# FIPI_shematics.net
KiCad netlist of a schematic drawn in EAGLE
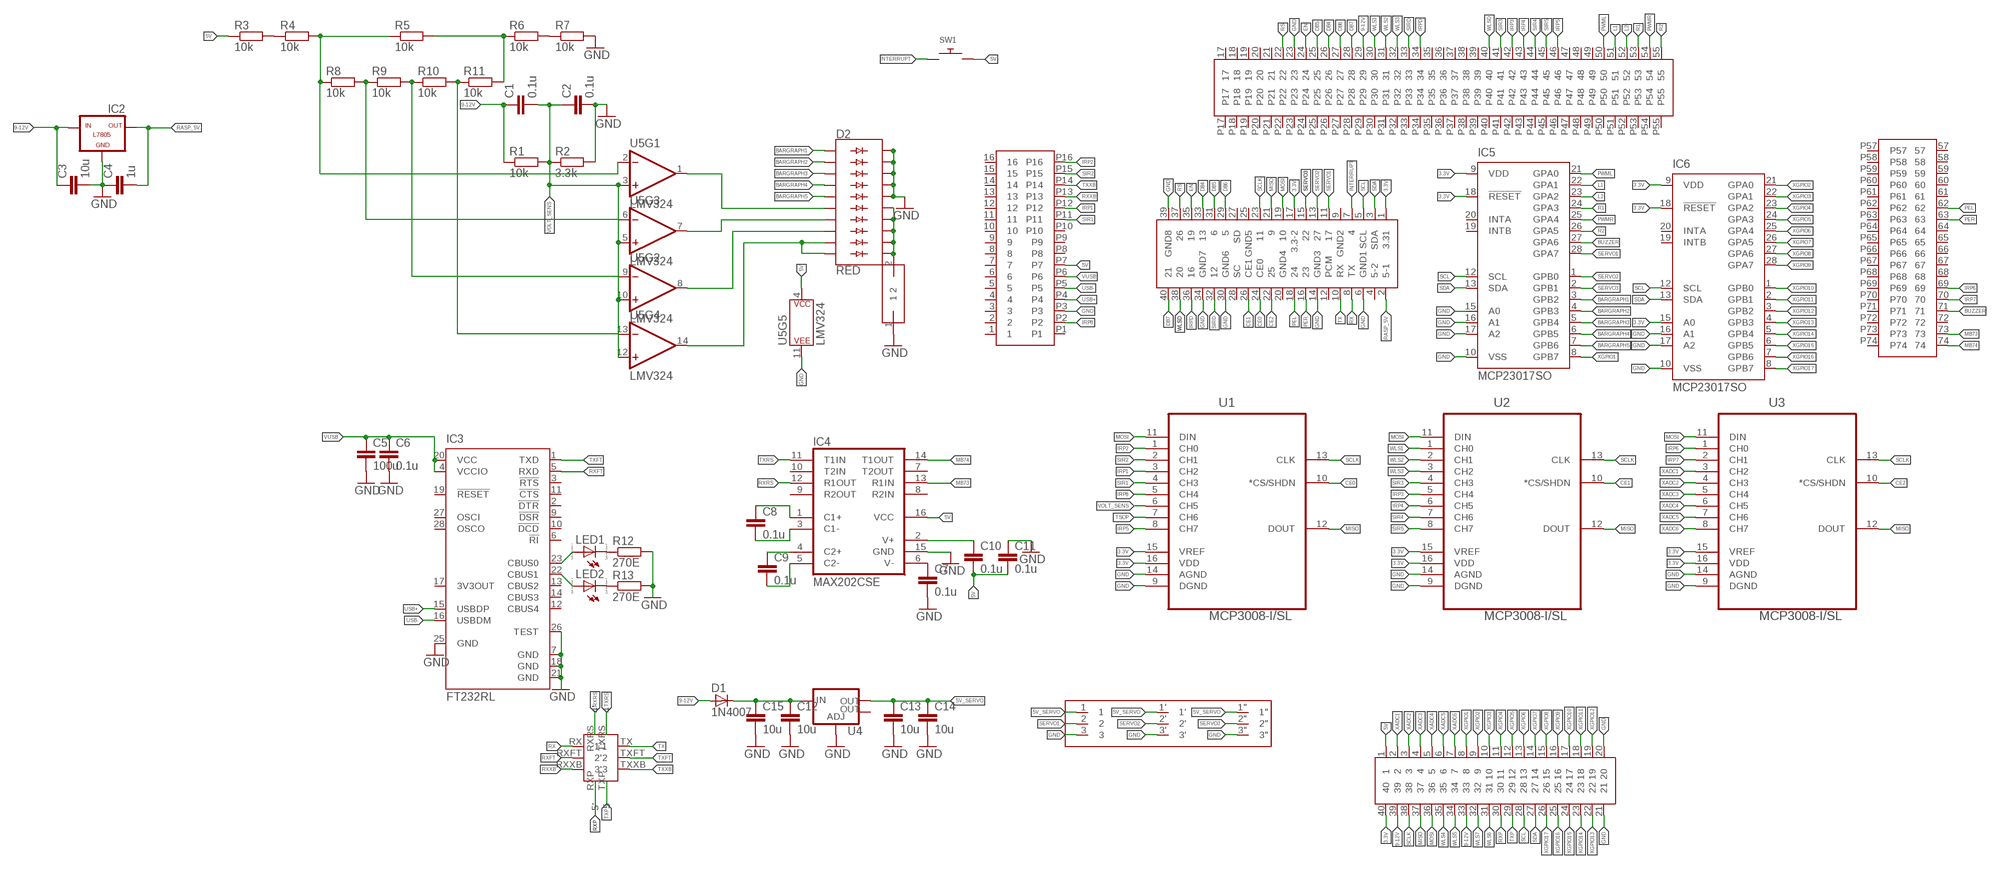
[diagram p0: schematic, sheet 1]

(export (version "E")
  (design (tool "Eeschema 10.0.6"))
  (components
    (comp (ref "C1")
      (value "0.1u")
      (footprint "eagle-import:C1206")
      (libsource (lib "eagle-import") (part "C-EUC1206"))
    )
    (comp (ref "C2")
      (value "0.1u")
      (footprint "eagle-import:C1206")
      (libsource (lib "eagle-import") (part "C-EUC1206"))
    )
    (comp (ref "C3")
      (value "10u")
      (footprint "eagle-import:C1206")
      (libsource (lib "eagle-import") (part "C-EUC1206"))
    )
    (comp (ref "C4")
      (value "1u")
      (footprint "eagle-import:C1206")
      (libsource (lib "eagle-import") (part "C-EUC1206"))
    )
    (comp (ref "C5")
      (value "100u")
      (footprint "eagle-import:C1206")
      (libsource (lib "eagle-import") (part "C-EUC1206"))
    )
    (comp (ref "C6")
      (value "0.1u")
      (footprint "eagle-import:C1206")
      (libsource (lib "eagle-import") (part "C-EUC1206"))
    )
    (comp (ref "C7")
      (value "0.1u")
      (footprint "eagle-import:C1206")
      (libsource (lib "eagle-import") (part "C-EUC1206"))
    )
    (comp (ref "C8")
      (value "0.1u")
      (footprint "eagle-import:C1206")
      (libsource (lib "eagle-import") (part "C-EUC1206"))
    )
    (comp (ref "C9")
      (value "0.1u")
      (footprint "eagle-import:C1206")
      (libsource (lib "eagle-import") (part "C-EUC1206"))
    )
    (comp (ref "C10")
      (value "0.1u")
      (footprint "eagle-import:C1206")
      (libsource (lib "eagle-import") (part "C-EUC1206"))
    )
    (comp (ref "C11")
      (value "0.1u")
      (footprint "eagle-import:C1206")
      (libsource (lib "eagle-import") (part "C-EUC1206"))
    )
    (comp (ref "C12")
      (value "10u")
      (footprint "eagle-import:C1206")
      (libsource (lib "eagle-import") (part "C-EUC1206"))
    )
    (comp (ref "C13")
      (value "10u")
      (footprint "eagle-import:C1206")
      (libsource (lib "eagle-import") (part "C-EUC1206"))
    )
    (comp (ref "C14")
      (value "10u")
      (footprint "eagle-import:C1206")
      (libsource (lib "eagle-import") (part "C-EUC1206"))
    )
    (comp (ref "C15")
      (value "10u")
      (footprint "eagle-import:C1206")
      (libsource (lib "eagle-import") (part "C-EUC1206"))
    )
    (comp (ref "D1")
      (value "1N4007")
      (footprint "eagle-import:SMA")
      (libsource (lib "eagle-import") (part "1N4007"))
    )
    (comp (ref "D2")
      (value "RED")
      (footprint "eagle-import:LED_BARGRAPH_10")
      (libsource (lib "eagle-import") (part "LED_BARGRAPH_10RED"))
    )
    (comp (ref "IC2")
      (value "L7805")
      (footprint "eagle-import:78XXL")
      (libsource (lib "eagle-import") (part "L7805"))
    )
    (comp (ref "IC3")
      (value "FT232RL")
      (footprint "eagle-import:SSOP28")
      (libsource (lib "eagle-import") (part "FT232RL"))
    )
    (comp (ref "IC4")
      (value "MAX202CSE")
      (footprint "eagle-import:SO16")
      (libsource (lib "eagle-import") (part "MAX202SEC"))
    )
    (comp (ref "IC5")
      (value "MCP23017SO")
      (footprint "eagle-import:SO28W")
      (libsource (lib "eagle-import") (part "MCP23017SO"))
    )
    (comp (ref "IC6")
      (value "MCP23017SO")
      (footprint "eagle-import:SO28W")
      (libsource (lib "eagle-import") (part "MCP23017SO"))
    )
    (comp (ref "LED1")
      (value "LED_E")
      (footprint "eagle-import:LED_1206")
      (libsource (lib "eagle-import") (part "LED_E"))
    )
    (comp (ref "LED2")
      (value "LED_E")
      (footprint "eagle-import:LED_1206")
      (libsource (lib "eagle-import") (part "LED_E"))
    )
    (comp (ref "R1")
      (value "10k")
      (footprint "eagle-import:M1206")
      (libsource (lib "eagle-import") (part "R-EU_M1206"))
    )
    (comp (ref "R2")
      (value "3.3k")
      (footprint "eagle-import:M1206")
      (libsource (lib "eagle-import") (part "R-EU_M1206"))
    )
    (comp (ref "R3")
      (value "10k")
      (footprint "eagle-import:M1206")
      (libsource (lib "eagle-import") (part "R-EU_M1206"))
    )
    (comp (ref "R4")
      (value "10k")
      (footprint "eagle-import:M1206")
      (libsource (lib "eagle-import") (part "R-EU_M1206"))
    )
    (comp (ref "R5")
      (value "10k")
      (footprint "eagle-import:M1206")
      (libsource (lib "eagle-import") (part "R-EU_M1206"))
    )
    (comp (ref "R6")
      (value "10k")
      (footprint "eagle-import:M1206")
      (libsource (lib "eagle-import") (part "R-EU_M1206"))
    )
    (comp (ref "R7")
      (value "10k")
      (footprint "eagle-import:M1206")
      (libsource (lib "eagle-import") (part "R-EU_M1206"))
    )
    (comp (ref "R8")
      (value "10k")
      (footprint "eagle-import:M1206")
      (libsource (lib "eagle-import") (part "R-EU_M1206"))
    )
    (comp (ref "R9")
      (value "10k")
      (footprint "eagle-import:M1206")
      (libsource (lib "eagle-import") (part "R-EU_M1206"))
    )
    (comp (ref "R10")
      (value "10k")
      (footprint "eagle-import:M1206")
      (libsource (lib "eagle-import") (part "R-EU_M1206"))
    )
    (comp (ref "R11")
      (value "10k")
      (footprint "eagle-import:M1206")
      (libsource (lib "eagle-import") (part "R-EU_M1206"))
    )
    (comp (ref "R12")
      (value "270E")
      (footprint "eagle-import:R1206")
      (libsource (lib "eagle-import") (part "R-EU_R1206"))
    )
    (comp (ref "R13")
      (value "270E")
      (footprint "eagle-import:R1206")
      (libsource (lib "eagle-import") (part "R-EU_R1206"))
    )
    (comp (ref "RASPPI")
      (value "MALE_HEADER")
      (footprint "eagle-import:MALE_HEADER_PACKAGE")
      (libsource (lib "eagle-import") (part "MALE_HEADER"))
    )
    (comp (ref "SW1")
      (value "SWITCH_PUSHBUTTONSOFTTOUCHSMD_SJ")
      (footprint "eagle-import:PUSHBUTTON_SMD_SJ")
      (libsource (lib "eagle-import") (part "SWITCH_PUSHBUTTONSOFTTOUCHSMD_SJ"))
    )
    (comp (ref "U$1")
      (value "BOARD")
      (footprint "eagle-import:FEMHEADER")
      (libsource (lib "eagle-import") (part "BOARD"))
    )
    (comp (ref "U$3")
      (value "SWITCH_RXTX")
      (footprint "eagle-import:SWITCH_RXTX")
      (libsource (lib "eagle-import") (part "SWITCH_RXTX"))
    )
    (comp (ref "U$4")
      (value "SWITCH1")
      (footprint "eagle-import:SWITCH1")
      (libsource (lib "eagle-import") (part "SWITCH1"))
    )
    (comp (ref "U$5")
      (value "PORT_EXP")
      (footprint "eagle-import:PORT_EXP")
      (libsource (lib "eagle-import") (part "PORT_EXP"))
    )
    (comp (ref "U$7")
      (value "SERVO")
      (footprint "eagle-import:SERVO")
      (libsource (lib "eagle-import") (part "SERVO"))
    )
    (comp (ref "U1")
      (value "MCP3008-I/SL")
      (footprint "eagle-import:SOIC127P600X175-16N")
      (fields (field (name "MF") "Microchip"))
      (libsource (lib "eagle-import") (part "MCP3008-I/SL"))
    )
    (comp (ref "U2")
      (value "MCP3008-I/SL")
      (footprint "eagle-import:SOIC127P600X175-16N")
      (fields (field (name "MF") "Microchip"))
      (libsource (lib "eagle-import") (part "MCP3008-I/SL"))
    )
    (comp (ref "U3")
      (value "MCP3008-I/SL")
      (footprint "eagle-import:SOIC127P600X175-16N")
      (fields (field (name "MF") "Microchip"))
      (libsource (lib "eagle-import") (part "MCP3008-I/SL"))
    )
    (comp (ref "U4")
      (value "V_REG_LM1117SOT223")
      (footprint "eagle-import:SOT223")
      (libsource (lib "eagle-import") (part "V_REG_LM1117SOT223"))
    )
    (comp (ref "U5")
      (value "LMV324")
      (footprint "eagle-import:SO14")
      (libsource (lib "eagle-import") (part "LMV324"))
    )
  )
  (nets
    (net (code "1") (name "3.3V") (class "Default")
      (node (ref "IC5") (pin "18") (pinfunction "~{RESET}_18") (pintype "input"))
      (node (ref "IC5") (pin "9") (pinfunction "VDD_9") (pintype "power_in"))
      (node (ref "IC6") (pin "15") (pinfunction "A0_15") (pintype "input"))
      (node (ref "IC6") (pin "18") (pinfunction "~{RESET}_18") (pintype "input"))
      (node (ref "IC6") (pin "9") (pinfunction "VDD_9") (pintype "power_in"))
      (node (ref "RASPPI") (pin "1") (pinfunction "3.31_1") (pintype "bidirectional"))
      (node (ref "RASPPI") (pin "17") (pinfunction "3.3-2_17") (pintype "bidirectional"))
      (node (ref "U$5") (pin "40") (pinfunction "40_40") (pintype "bidirectional"))
      (node (ref "U1") (pin "15") (pinfunction "VREF_15") (pintype "input"))
      (node (ref "U1") (pin "16") (pinfunction "VDD_16") (pintype "power_in"))
      (node (ref "U2") (pin "15") (pinfunction "VREF_15") (pintype "input"))
      (node (ref "U2") (pin "16") (pinfunction "VDD_16") (pintype "power_in"))
      (node (ref "U3") (pin "15") (pinfunction "VREF_15") (pintype "input"))
      (node (ref "U3") (pin "16") (pinfunction "VDD_16") (pintype "power_in"))
    )
    (net (code "2") (name "5V") (class "Default")
      (node (ref "C10") (pin "2") (pinfunction "2_2") (pintype "passive"))
      (node (ref "C11") (pin "2") (pinfunction "2_2") (pintype "passive"))
      (node (ref "IC4") (pin "16") (pinfunction "VCC_16") (pintype "power_in"))
      (node (ref "R3") (pin "1") (pinfunction "1_1") (pintype "passive"))
      (node (ref "SW1") (pin "P$2") (pinfunction "P$2_P$2") (pintype "passive"))
      (node (ref "U$1") (pin "P7") (pinfunction "P7_P7") (pintype "bidirectional"))
      (node (ref "U$5") (pin "1") (pinfunction "1_1") (pintype "bidirectional"))
      (node (ref "U5") (pin "4") (pinfunction "P$V+_4") (pintype "bidirectional"))
    )
    (net (code "3") (name "5V_SERVO") (class "Default")
      (node (ref "C13") (pin "1") (pinfunction "1_1") (pintype "passive"))
      (node (ref "C14") (pin "1") (pinfunction "1_1") (pintype "passive"))
      (node (ref "U$7") (pin "1") (pinfunction "1_1") (pintype "bidirectional"))
      (node (ref "U$7") (pin "1\"") (pinfunction "1\"_1\"") (pintype "bidirectional"))
      (node (ref "U$7") (pin "1'") (pinfunction "1'_1'") (pintype "bidirectional"))
      (node (ref "U4") (pin "2") (pinfunction "OUT_2") (pintype "output"))
    )
    (net (code "4") (name "9-12V") (class "Default")
      (node (ref "C1") (pin "1") (pinfunction "1_1") (pintype "passive"))
      (node (ref "C3") (pin "1") (pinfunction "1_1") (pintype "passive"))
      (node (ref "D1") (pin "A") (pinfunction "A_A") (pintype "passive"))
      (node (ref "IC2") (pin "IN") (pinfunction "IN_IN") (pintype "input"))
      (node (ref "R1") (pin "1") (pinfunction "1_1") (pintype "passive"))
      (node (ref "U$1") (pin "29") (pinfunction "29_29") (pintype "bidirectional"))
      (node (ref "U$5") (pin "33") (pinfunction "33_33") (pintype "bidirectional"))
      (node (ref "U$5") (pin "39") (pinfunction "39_39") (pintype "bidirectional"))
    )
    (net (code "5") (name "BARGRAPH1") (class "Default")
      (node (ref "D2") (pin "1") (pinfunction "A_1") (pintype "passive"))
      (node (ref "IC5") (pin "3") (pinfunction "GPB2_3") (pintype "bidirectional"))
    )
    (net (code "6") (name "BARGRAPH2") (class "Default")
      (node (ref "D2") (pin "2") (pinfunction "A1_2") (pintype "passive"))
      (node (ref "IC5") (pin "4") (pinfunction "GPB3_4") (pintype "bidirectional"))
    )
    (net (code "7") (name "BARGRAPH3") (class "Default")
      (node (ref "D2") (pin "3") (pinfunction "A2_3") (pintype "passive"))
      (node (ref "IC5") (pin "5") (pinfunction "GPB4_5") (pintype "bidirectional"))
    )
    (net (code "8") (name "BARGRAPH4") (class "Default")
      (node (ref "D2") (pin "4") (pinfunction "A3_4") (pintype "passive"))
      (node (ref "IC5") (pin "6") (pinfunction "GPB5_6") (pintype "bidirectional"))
    )
    (net (code "9") (name "BARGRAPH5") (class "Default")
      (node (ref "D2") (pin "5") (pinfunction "A4_5") (pintype "passive"))
      (node (ref "IC5") (pin "7") (pinfunction "GPB6_7") (pintype "bidirectional"))
    )
    (net (code "10") (name "BUZZER") (class "Default")
      (node (ref "IC5") (pin "27") (pinfunction "GPA6_27") (pintype "bidirectional"))
      (node (ref "U$1") (pin "71") (pinfunction "71_71") (pintype "bidirectional"))
    )
    (net (code "11") (name "CE0") (class "Default")
      (node (ref "RASPPI") (pin "24") (pinfunction "CE0_24") (pintype "bidirectional"))
      (node (ref "U1") (pin "10") (pinfunction "*CS/SHDN_10") (pintype "input"))
    )
    (net (code "12") (name "CE1") (class "Default")
      (node (ref "RASPPI") (pin "26") (pinfunction "CE1_26") (pintype "bidirectional"))
      (node (ref "U2") (pin "10") (pinfunction "*CS/SHDN_10") (pintype "input"))
    )
    (net (code "13") (name "CE2") (class "Default")
      (node (ref "RASPPI") (pin "22") (pinfunction "25_22") (pintype "bidirectional"))
      (node (ref "U3") (pin "10") (pinfunction "*CS/SHDN_10") (pintype "input"))
    )
    (net (code "14") (name "DB4") (class "Default")
      (node (ref "RASPPI") (pin "33") (pinfunction "13_33") (pintype "bidirectional"))
      (node (ref "U$1") (pin "26") (pinfunction "26_26") (pintype "bidirectional"))
    )
    (net (code "15") (name "DB5") (class "Default")
      (node (ref "RASPPI") (pin "31") (pinfunction "6_31") (pintype "bidirectional"))
      (node (ref "U$1") (pin "25") (pinfunction "25_25") (pintype "bidirectional"))
    )
    (net (code "16") (name "DB6") (class "Default")
      (node (ref "RASPPI") (pin "29") (pinfunction "5_29") (pintype "bidirectional"))
      (node (ref "U$1") (pin "27") (pinfunction "27_27") (pintype "bidirectional"))
    )
    (net (code "17") (name "DB7") (class "Default")
      (node (ref "RASPPI") (pin "40") (pinfunction "21_40") (pintype "bidirectional"))
      (node (ref "U$1") (pin "28") (pinfunction "28_28") (pintype "bidirectional"))
    )
    (net (code "18") (name "EN") (class "Default")
      (node (ref "RASPPI") (pin "35") (pinfunction "19_35") (pintype "bidirectional"))
      (node (ref "U$1") (pin "24") (pinfunction "24_24") (pintype "bidirectional"))
    )
    (net (code "19") (name "GND") (class "Default")
      (node (ref "C11") (pin "1") (pinfunction "1_1") (pintype "passive"))
      (node (ref "C12") (pin "2") (pinfunction "2_2") (pintype "passive"))
      (node (ref "C13") (pin "2") (pinfunction "2_2") (pintype "passive"))
      (node (ref "C14") (pin "2") (pinfunction "2_2") (pintype "passive"))
      (node (ref "C15") (pin "2") (pinfunction "2_2") (pintype "passive"))
      (node (ref "C2") (pin "2") (pinfunction "2_2") (pintype "passive"))
      (node (ref "C3") (pin "2") (pinfunction "2_2") (pintype "passive"))
      (node (ref "C4") (pin "1") (pinfunction "1_1") (pintype "passive"))
      (node (ref "C5") (pin "2") (pinfunction "2_2") (pintype "passive"))
      (node (ref "C6") (pin "2") (pinfunction "2_2") (pintype "passive"))
      (node (ref "C7") (pin "2") (pinfunction "2_2") (pintype "passive"))
      (node (ref "D2") (pin "16") (pinfunction "C4_16") (pintype "passive"))
      (node (ref "D2") (pin "17") (pinfunction "C3_17") (pintype "passive"))
      (node (ref "D2") (pin "18") (pinfunction "C2_18") (pintype "passive"))
      (node (ref "D2") (pin "19") (pinfunction "C1_19") (pintype "passive"))
      (node (ref "D2") (pin "20") (pinfunction "C_20") (pintype "passive"))
      (node (ref "IC2") (pin "GND") (pinfunction "GND_GND") (pintype "input"))
      (node (ref "IC3") (pin "18") (pinfunction "GND_18") (pintype "power_in"))
      (node (ref "IC3") (pin "21") (pinfunction "GND_21") (pintype "power_in"))
      (node (ref "IC3") (pin "25") (pinfunction "GND_25") (pintype "power_in"))
      (node (ref "IC3") (pin "26") (pinfunction "TEST_26") (pintype "input"))
      (node (ref "IC3") (pin "7") (pinfunction "GND_7") (pintype "power_in"))
      (node (ref "IC4") (pin "15") (pinfunction "GND_15") (pintype "power_in"))
      (node (ref "IC5") (pin "10") (pinfunction "VSS_10") (pintype "power_in"))
      (node (ref "IC5") (pin "15") (pinfunction "A0_15") (pintype "input"))
      (node (ref "IC5") (pin "16") (pinfunction "A1_16") (pintype "input"))
      (node (ref "IC5") (pin "17") (pinfunction "A2_17") (pintype "input"))
      (node (ref "IC6") (pin "10") (pinfunction "VSS_10") (pintype "power_in"))
      (node (ref "IC6") (pin "16") (pinfunction "A1_16") (pintype "input"))
      (node (ref "IC6") (pin "17") (pinfunction "A2_17") (pintype "input"))
      (node (ref "R12") (pin "2") (pinfunction "2_2") (pintype "passive"))
      (node (ref "R13") (pin "2") (pinfunction "2_2") (pintype "passive"))
      (node (ref "R2") (pin "2") (pinfunction "2_2") (pintype "passive"))
      (node (ref "R7") (pin "2") (pinfunction "2_2") (pintype "passive"))
      (node (ref "RASPPI") (pin "14") (pinfunction "GND3_14") (pintype "bidirectional"))
      (node (ref "RASPPI") (pin "30") (pinfunction "GND6_30") (pintype "bidirectional"))
      (node (ref "RASPPI") (pin "34") (pinfunction "GND7_34") (pintype "bidirectional"))
      (node (ref "RASPPI") (pin "39") (pinfunction "GND8_39") (pintype "bidirectional"))
      (node (ref "RASPPI") (pin "6") (pinfunction "GND1_6") (pintype "bidirectional"))
      (node (ref "U$1") (pin "23") (pinfunction "23_23") (pintype "bidirectional"))
      (node (ref "U$1") (pin "P3") (pinfunction "P3_P3") (pintype "bidirectional"))
      (node (ref "U$4") (pin "1") (pinfunction "1_1") (pintype "bidirectional"))
      (node (ref "U$5") (pin "20") (pinfunction "20_20") (pintype "bidirectional"))
      (node (ref "U$5") (pin "21") (pinfunction "21_21") (pintype "bidirectional"))
      (node (ref "U$7") (pin "3") (pinfunction "3_3") (pintype "bidirectional"))
      (node (ref "U$7") (pin "3\"") (pinfunction "3\"_3\"") (pintype "bidirectional"))
      (node (ref "U$7") (pin "3'") (pinfunction "3'_3'") (pintype "bidirectional"))
      (node (ref "U1") (pin "14") (pinfunction "AGND_14") (pintype "passive"))
      (node (ref "U1") (pin "9") (pinfunction "DGND_9") (pintype "passive"))
      (node (ref "U2") (pin "14") (pinfunction "AGND_14") (pintype "passive"))
      (node (ref "U2") (pin "9") (pinfunction "DGND_9") (pintype "passive"))
      (node (ref "U3") (pin "14") (pinfunction "AGND_14") (pintype "passive"))
      (node (ref "U3") (pin "9") (pinfunction "DGND_9") (pintype "passive"))
      (node (ref "U4") (pin "1") (pinfunction "ADJ_1") (pintype "input"))
      (node (ref "U5") (pin "11") (pinfunction "P$V-_11") (pintype "bidirectional"))
    )
    (net (code "20") (name "INTERRUPT") (class "Default")
      (node (ref "RASPPI") (pin "7") (pinfunction "4_7") (pintype "bidirectional"))
      (node (ref "SW1") (pin "P$1") (pinfunction "P$1_P$1") (pintype "passive"))
    )
    (net (code "21") (name "IRP1") (class "Default")
      (node (ref "U$1") (pin "P12") (pinfunction "P12_P12") (pintype "bidirectional"))
      (node (ref "U1") (pin "3") (pinfunction "CH2_3") (pintype "input"))
    )
    (net (code "22") (name "IRP2") (class "Default")
      (node (ref "U$1") (pin "P16") (pinfunction "P16_P16") (pintype "bidirectional"))
      (node (ref "U1") (pin "1") (pinfunction "CH0_1") (pintype "input"))
    )
    (net (code "23") (name "IRP3") (class "Default")
      (node (ref "U$1") (pin "42") (pinfunction "42_42") (pintype "bidirectional"))
      (node (ref "U2") (pin "5") (pinfunction "CH4_5") (pintype "input"))
    )
    (net (code "24") (name "IRP4") (class "Default")
      (node (ref "U$1") (pin "43") (pinfunction "43_43") (pintype "bidirectional"))
      (node (ref "U2") (pin "6") (pinfunction "CH5_6") (pintype "input"))
    )
    (net (code "25") (name "IRP5") (class "Default")
      (node (ref "U$1") (pin "46") (pinfunction "46_46") (pintype "bidirectional"))
      (node (ref "U1") (pin "8") (pinfunction "CH7_8") (pintype "input"))
    )
    (net (code "26") (name "IRP6") (class "Default")
      (node (ref "U$1") (pin "69") (pinfunction "69_69") (pintype "bidirectional"))
      (node (ref "U3") (pin "1") (pinfunction "CH0_1") (pintype "input"))
    )
    (net (code "27") (name "IRP7") (class "Default")
      (node (ref "U$1") (pin "70") (pinfunction "70_70") (pintype "bidirectional"))
      (node (ref "U3") (pin "2") (pinfunction "CH1_2") (pintype "input"))
    )
    (net (code "28") (name "IRP8") (class "Default")
      (node (ref "U$1") (pin "P2") (pinfunction "P2_P2") (pintype "bidirectional"))
      (node (ref "U1") (pin "5") (pinfunction "CH4_5") (pintype "input"))
    )
    (net (code "29") (name "IRPD") (class "Default")
      (node (ref "RASPPI") (pin "36") (pinfunction "16_36") (pintype "bidirectional"))
      (node (ref "U$1") (pin "34") (pinfunction "34_34") (pintype "bidirectional"))
    )
    (net (code "30") (name "L1") (class "Default")
      (node (ref "IC5") (pin "22") (pinfunction "GPA1_22") (pintype "bidirectional"))
      (node (ref "U$1") (pin "51") (pinfunction "51_51") (pintype "bidirectional"))
    )
    (net (code "31") (name "L2") (class "Default")
      (node (ref "IC5") (pin "23") (pinfunction "GPA2_23") (pintype "bidirectional"))
      (node (ref "U$1") (pin "52") (pinfunction "52_52") (pintype "bidirectional"))
    )
    (net (code "32") (name "MB73") (class "Default")
      (node (ref "IC4") (pin "13") (pinfunction "R1IN_13") (pintype "input"))
      (node (ref "U$1") (pin "73") (pinfunction "73_73") (pintype "bidirectional"))
    )
    (net (code "33") (name "MB74") (class "Default")
      (node (ref "IC4") (pin "14") (pinfunction "T1OUT_14") (pintype "output"))
      (node (ref "U$1") (pin "74") (pinfunction "74_74") (pintype "bidirectional"))
    )
    (net (code "34") (name "MISO") (class "Default")
      (node (ref "RASPPI") (pin "21") (pinfunction "9_21") (pintype "bidirectional"))
      (node (ref "U$5") (pin "37") (pinfunction "37_37") (pintype "bidirectional"))
      (node (ref "U1") (pin "12") (pinfunction "DOUT_12") (pintype "output"))
      (node (ref "U2") (pin "12") (pinfunction "DOUT_12") (pintype "output"))
      (node (ref "U3") (pin "12") (pinfunction "DOUT_12") (pintype "output"))
    )
    (net (code "35") (name "MOSI") (class "Default")
      (node (ref "RASPPI") (pin "19") (pinfunction "10_19") (pintype "bidirectional"))
      (node (ref "U$5") (pin "36") (pinfunction "36_36") (pintype "bidirectional"))
      (node (ref "U1") (pin "11") (pinfunction "DIN_11") (pintype "input"))
      (node (ref "U2") (pin "11") (pinfunction "DIN_11") (pintype "input"))
      (node (ref "U3") (pin "11") (pinfunction "DIN_11") (pintype "input"))
    )
    (net (code "36") (name "Net-(D1-C)") (class "Default")
      (node (ref "C12") (pin "1") (pinfunction "1_1") (pintype "passive"))
      (node (ref "C15") (pin "1") (pinfunction "1_1") (pintype "passive"))
      (node (ref "D1") (pin "K") (pinfunction "C_K") (pintype "passive"))
      (node (ref "U4") (pin "3") (pinfunction "IN_3") (pintype "input"))
    )
    (net (code "37") (name "Net-(D2-A5)") (class "Default")
      (node (ref "D2") (pin "6") (pinfunction "A5_6") (pintype "passive"))
      (node (ref "U5") (pin "1") (pinfunction "OUT_1") (pintype "output"))
    )
    (net (code "38") (name "Net-(D2-A6)") (class "Default")
      (node (ref "D2") (pin "7") (pinfunction "A6_7") (pintype "passive"))
      (node (ref "U5") (pin "7") (pinfunction "OUT_7") (pintype "output"))
    )
    (net (code "39") (name "Net-(D2-A7)") (class "Default")
      (node (ref "D2") (pin "8") (pinfunction "A7_8") (pintype "passive"))
      (node (ref "U5") (pin "8") (pinfunction "OUT_8") (pintype "output"))
    )
    (net (code "40") (name "Net-(D2-A8)") (class "Default")
      (node (ref "D2") (pin "10") (pinfunction "A9_10") (pintype "passive"))
      (node (ref "D2") (pin "9") (pinfunction "A8_9") (pintype "passive"))
      (node (ref "U5") (pin "14") (pinfunction "OUT_14") (pintype "output"))
    )
    (net (code "41") (name "Net-(D2-C5)") (class "Default")
      (node (ref "D2") (pin "11") (pinfunction "C9_11") (pintype "passive"))
      (node (ref "D2") (pin "12") (pinfunction "C8_12") (pintype "passive"))
      (node (ref "D2") (pin "13") (pinfunction "C7_13") (pintype "passive"))
      (node (ref "D2") (pin "14") (pinfunction "C6_14") (pintype "passive"))
      (node (ref "D2") (pin "15") (pinfunction "C5_15") (pintype "passive"))
      (node (ref "U$4") (pin "2") (pinfunction "2_2") (pintype "bidirectional"))
    )
    (net (code "42") (name "Net-(IC3-CBUS0)") (class "Default")
      (node (ref "IC3") (pin "23") (pinfunction "CBUS0_23") (pintype "bidirectional"))
      (node (ref "LED1") (pin "A") (pinfunction "A_A") (pintype "passive"))
    )
    (net (code "43") (name "Net-(IC3-CBUS1)") (class "Default")
      (node (ref "IC3") (pin "22") (pinfunction "CBUS1_22") (pintype "bidirectional"))
      (node (ref "LED2") (pin "A") (pinfunction "A_A") (pintype "passive"))
    )
    (net (code "44") (name "Net-(IC4-C1+)") (class "Default")
      (node (ref "C8") (pin "1") (pinfunction "1_1") (pintype "passive"))
      (node (ref "IC4") (pin "1") (pinfunction "C1+_1") (pintype "passive"))
    )
    (net (code "45") (name "Net-(IC4-C1-)") (class "Default")
      (node (ref "C8") (pin "2") (pinfunction "2_2") (pintype "passive"))
      (node (ref "IC4") (pin "3") (pinfunction "C1-_3") (pintype "passive"))
    )
    (net (code "46") (name "Net-(IC4-C2+)") (class "Default")
      (node (ref "C9") (pin "1") (pinfunction "1_1") (pintype "passive"))
      (node (ref "IC4") (pin "4") (pinfunction "C2+_4") (pintype "passive"))
    )
    (net (code "47") (name "Net-(IC4-C2-)") (class "Default")
      (node (ref "C9") (pin "2") (pinfunction "2_2") (pintype "passive"))
      (node (ref "IC4") (pin "5") (pinfunction "C2-_5") (pintype "passive"))
    )
    (net (code "48") (name "Net-(IC4-V+)") (class "Default")
      (node (ref "C10") (pin "1") (pinfunction "1_1") (pintype "passive"))
      (node (ref "IC4") (pin "2") (pinfunction "V+_2") (pintype "power_in"))
    )
    (net (code "49") (name "Net-(IC4-V-)") (class "Default")
      (node (ref "C7") (pin "1") (pinfunction "1_1") (pintype "passive"))
      (node (ref "IC4") (pin "6") (pinfunction "V-_6") (pintype "power_in"))
    )
    (net (code "50") (name "Net-(LED1-PadC)") (class "Default")
      (node (ref "LED1") (pin "C") (pinfunction "C_C") (pintype "passive"))
      (node (ref "R12") (pin "1") (pinfunction "1_1") (pintype "passive"))
    )
    (net (code "51") (name "Net-(LED2-PadC)") (class "Default")
      (node (ref "LED2") (pin "C") (pinfunction "C_C") (pintype "passive"))
      (node (ref "R13") (pin "1") (pinfunction "1_1") (pintype "passive"))
    )
    (net (code "52") (name "Net-(R3-Pad2)") (class "Default")
      (node (ref "R3") (pin "2") (pinfunction "2_2") (pintype "passive"))
      (node (ref "R4") (pin "1") (pinfunction "1_1") (pintype "passive"))
    )
    (net (code "53") (name "Net-(R6-Pad2)") (class "Default")
      (node (ref "R6") (pin "2") (pinfunction "2_2") (pintype "passive"))
      (node (ref "R7") (pin "1") (pinfunction "1_1") (pintype "passive"))
    )
    (net (code "54") (name "Net-(R11-Pad2)") (class "Default")
      (node (ref "R11") (pin "2") (pinfunction "2_2") (pintype "passive"))
      (node (ref "R5") (pin "2") (pinfunction "2_2") (pintype "passive"))
      (node (ref "R6") (pin "1") (pinfunction "1_1") (pintype "passive"))
    )
    (net (code "55") (name "Net-(U5A--IN)") (class "Default")
      (node (ref "R4") (pin "2") (pinfunction "2_2") (pintype "passive"))
      (node (ref "R5") (pin "1") (pinfunction "1_1") (pintype "passive"))
      (node (ref "R8") (pin "1") (pinfunction "1_1") (pintype "passive"))
      (node (ref "U5") (pin "2") (pinfunction "-IN_2") (pintype "input"))
    )
    (net (code "56") (name "Net-(U5B--IN)") (class "Default")
      (node (ref "R10") (pin "1") (pinfunction "1_1") (pintype "passive"))
      (node (ref "R9") (pin "2") (pinfunction "2_2") (pintype "passive"))
      (node (ref "U5") (pin "9") (pinfunction "-IN_9") (pintype "input"))
    )
    (net (code "57") (name "Net-(U5C--IN)") (class "Default")
      (node (ref "R8") (pin "2") (pinfunction "2_2") (pintype "passive"))
      (node (ref "R9") (pin "1") (pinfunction "1_1") (pintype "passive"))
      (node (ref "U5") (pin "6") (pinfunction "-IN_6") (pintype "input"))
    )
    (net (code "58") (name "Net-(U5D--IN)") (class "Default")
      (node (ref "R10") (pin "2") (pinfunction "2_2") (pintype "passive"))
      (node (ref "R11") (pin "1") (pinfunction "1_1") (pintype "passive"))
      (node (ref "U5") (pin "13") (pinfunction "-IN_13") (pintype "input"))
    )
    (net (code "59") (name "PEL") (class "Default")
      (node (ref "RASPPI") (pin "18") (pinfunction "24_18") (pintype "bidirectional"))
      (node (ref "U$1") (pin "62") (pinfunction "62_62") (pintype "bidirectional"))
    )
    (net (code "60") (name "PER") (class "Default")
      (node (ref "RASPPI") (pin "16") (pinfunction "23_16") (pintype "bidirectional"))
      (node (ref "U$1") (pin "63") (pinfunction "63_63") (pintype "bidirectional"))
    )
    (net (code "61") (name "PWML") (class "Default")
      (node (ref "IC5") (pin "21") (pinfunction "GPA0_21") (pintype "bidirectional"))
      (node (ref "U$1") (pin "50") (pinfunction "50_50") (pintype "bidirectional"))
    )
    (net (code "62") (name "PWMR") (class "Default")
      (node (ref "IC5") (pin "25") (pinfunction "GPA4_25") (pintype "bidirectional"))
      (node (ref "U$1") (pin "54") (pinfunction "54_54") (pintype "bidirectional"))
    )
    (net (code "63") (name "R1") (class "Default")
      (node (ref "IC5") (pin "24") (pinfunction "GPA3_24") (pintype "bidirectional"))
      (node (ref "U$1") (pin "53") (pinfunction "53_53") (pintype "bidirectional"))
    )
    (net (code "64") (name "R2") (class "Default")
      (node (ref "IC5") (pin "26") (pinfunction "GPA5_26") (pintype "bidirectional"))
      (node (ref "U$1") (pin "55") (pinfunction "55_55") (pintype "bidirectional"))
    )
    (net (code "65") (name "RASP_5V") (class "Default")
      (node (ref "C4") (pin "2") (pinfunction "2_2") (pintype "passive"))
      (node (ref "IC2") (pin "OUT") (pinfunction "OUT_OUT") (pintype "passive"))
      (node (ref "RASPPI") (pin "2") (pinfunction "5-1_2") (pintype "bidirectional"))
    )
    (net (code "66") (name "RS") (class "Default")
      (node (ref "RASPPI") (pin "37") (pinfunction "26_37") (pintype "bidirectional"))
      (node (ref "U$1") (pin "22") (pinfunction "22_22") (pintype "bidirectional"))
    )
    (net (code "67") (name "RX") (class "Default")
      (node (ref "RASPPI") (pin "8") (pinfunction "TX_8") (pintype "bidirectional"))
      (node (ref "U$3") (pin "RX") (pinfunction "1'_RX") (pintype "bidirectional"))
    )
    (net (code "68") (name "RXFT") (class "Default")
      (node (ref "IC3") (pin "5") (pinfunction "RXD_5") (pintype "input"))
      (node (ref "U$3") (pin "RXFT") (pinfunction "2'_RXFT") (pintype "bidirectional"))
    )
    (net (code "69") (name "RXP") (class "Default")
      (node (ref "U$3") (pin "RXP") (pinfunction "5'_RXP") (pintype "bidirectional"))
      (node (ref "U$5") (pin "30") (pinfunction "30_30") (pintype "bidirectional"))
    )
    (net (code "70") (name "RXRS") (class "Default")
      (node (ref "IC4") (pin "12") (pinfunction "R1OUT_12") (pintype "output"))
      (node (ref "U$3") (pin "RXRS") (pinfunction "4'_RXRS") (pintype "bidirectional"))
    )
    (net (code "71") (name "RXXB") (class "Default")
      (node (ref "U$1") (pin "P13") (pinfunction "P13_P13") (pintype "bidirectional"))
      (node (ref "U$3") (pin "RXXB") (pinfunction "3'_RXXB") (pintype "bidirectional"))
    )
    (net (code "72") (name "SCL") (class "Default")
      (node (ref "IC5") (pin "12") (pinfunction "SCL_12") (pintype "input"))
      (node (ref "IC6") (pin "12") (pinfunction "SCL_12") (pintype "input"))
      (node (ref "RASPPI") (pin "5") (pinfunction "SCL_5") (pintype "bidirectional"))
      (node (ref "U$5") (pin "28") (pinfunction "28_28") (pintype "bidirectional"))
    )
    (net (code "73") (name "SCLK") (class "Default")
      (node (ref "RASPPI") (pin "23") (pinfunction "11_23") (pintype "bidirectional"))
      (node (ref "U$5") (pin "38") (pinfunction "38_38") (pintype "bidirectional"))
      (node (ref "U1") (pin "13") (pinfunction "CLK_13") (pintype "input"))
      (node (ref "U2") (pin "13") (pinfunction "CLK_13") (pintype "input"))
      (node (ref "U3") (pin "13") (pinfunction "CLK_13") (pintype "input"))
    )
    (net (code "74") (name "SDA") (class "Default")
      (node (ref "IC5") (pin "13") (pinfunction "SDA_13") (pintype "bidirectional"))
      (node (ref "IC6") (pin "13") (pinfunction "SDA_13") (pintype "bidirectional"))
      (node (ref "RASPPI") (pin "3") (pinfunction "SDA_3") (pintype "bidirectional"))
      (node (ref "U$5") (pin "27") (pinfunction "27_27") (pintype "bidirectional"))
    )
    (net (code "75") (name "SERVO1") (class "Default")
      (node (ref "IC5") (pin "28") (pinfunction "GPA7_28") (pintype "bidirectional"))
      (node (ref "RASPPI") (pin "11") (pinfunction "17_11") (pintype "bidirectional"))
      (node (ref "U$7") (pin "2") (pinfunction "2_2") (pintype "bidirectional"))
    )
    (net (code "76") (name "SERVO2") (class "Default")
      (node (ref "IC5") (pin "1") (pinfunction "GPB0_1") (pintype "bidirectional"))
      (node (ref "RASPPI") (pin "13") (pinfunction "27_13") (pintype "bidirectional"))
      (node (ref "U$7") (pin "2'") (pinfunction "2'_2'") (pintype "bidirectional"))
    )
    (net (code "77") (name "SERVO3") (class "Default")
      (node (ref "IC5") (pin "2") (pinfunction "GPB1_2") (pintype "bidirectional"))
      (node (ref "RASPPI") (pin "15") (pinfunction "22_15") (pintype "bidirectional"))
      (node (ref "U$7") (pin "2\"") (pinfunction "2\"_2\"") (pintype "bidirectional"))
    )
    (net (code "78") (name "SIR1") (class "Default")
      (node (ref "U$1") (pin "P11") (pinfunction "P11_P11") (pintype "bidirectional"))
      (node (ref "U1") (pin "4") (pinfunction "CH3_4") (pintype "input"))
    )
    (net (code "79") (name "SIR2") (class "Default")
      (node (ref "U$1") (pin "P15") (pinfunction "P15_P15") (pintype "bidirectional"))
      (node (ref "U1") (pin "2") (pinfunction "CH1_2") (pintype "input"))
    )
    (net (code "80") (name "SIR3") (class "Default")
      (node (ref "U$1") (pin "41") (pinfunction "41_41") (pintype "bidirectional"))
      (node (ref "U2") (pin "4") (pinfunction "CH3_4") (pintype "input"))
    )
    (net (code "81") (name "SIR4") (class "Default")
      (node (ref "U$1") (pin "44") (pinfunction "44_44") (pintype "bidirectional"))
      (node (ref "U2") (pin "7") (pinfunction "CH6_7") (pintype "input"))
    )
    (net (code "82") (name "SIR5") (class "Default")
      (node (ref "U$1") (pin "45") (pinfunction "45_45") (pintype "bidirectional"))
      (node (ref "U2") (pin "8") (pinfunction "CH7_8") (pintype "input"))
    )
    (net (code "83") (name "SIRD") (class "Default")
      (node (ref "RASPPI") (pin "32") (pinfunction "12_32") (pintype "bidirectional"))
      (node (ref "U$1") (pin "33") (pinfunction "33_33") (pintype "bidirectional"))
    )
    (net (code "84") (name "TSOP") (class "Default")
      (node (ref "U1") (pin "7") (pinfunction "CH6_7") (pintype "input"))
    )
    (net (code "85") (name "TX") (class "Default")
      (node (ref "RASPPI") (pin "10") (pinfunction "RX_10") (pintype "bidirectional"))
      (node (ref "U$3") (pin "TX") (pinfunction "1_TX") (pintype "bidirectional"))
    )
    (net (code "86") (name "TXFT") (class "Default")
      (node (ref "IC3") (pin "1") (pinfunction "TXD_1") (pintype "output"))
      (node (ref "U$3") (pin "TXFT") (pinfunction "2_TXFT") (pintype "bidirectional"))
    )
    (net (code "87") (name "TXP") (class "Default")
      (node (ref "U$3") (pin "TXP") (pinfunction "5_TXP") (pintype "bidirectional"))
      (node (ref "U$5") (pin "29") (pinfunction "29_29") (pintype "bidirectional"))
    )
    (net (code "88") (name "TXRS") (class "Default")
      (node (ref "IC4") (pin "11") (pinfunction "T1IN_11") (pintype "input"))
      (node (ref "U$3") (pin "TXRS") (pinfunction "4_TXRS") (pintype "bidirectional"))
    )
    (net (code "89") (name "TXXB") (class "Default")
      (node (ref "U$1") (pin "P14") (pinfunction "P14_P14") (pintype "bidirectional"))
      (node (ref "U$3") (pin "TXXB") (pinfunction "3_TXXB") (pintype "bidirectional"))
    )
    (net (code "90") (name "USB+") (class "Default")
      (node (ref "IC3") (pin "15") (pinfunction "USBDP_15") (pintype "bidirectional"))
      (node (ref "U$1") (pin "P4") (pinfunction "P4_P4") (pintype "bidirectional"))
    )
    (net (code "91") (name "USB-") (class "Default")
      (node (ref "IC3") (pin "16") (pinfunction "USBDM_16") (pintype "bidirectional"))
      (node (ref "U$1") (pin "P5") (pinfunction "P5_P5") (pintype "bidirectional"))
    )
    (net (code "92") (name "VOLT_SENS") (class "Default")
      (node (ref "C1") (pin "2") (pinfunction "2_2") (pintype "passive"))
      (node (ref "C2") (pin "1") (pinfunction "1_1") (pintype "passive"))
      (node (ref "R1") (pin "2") (pinfunction "2_2") (pintype "passive"))
      (node (ref "R2") (pin "1") (pinfunction "1_1") (pintype "passive"))
      (node (ref "U1") (pin "6") (pinfunction "CH5_6") (pintype "input"))
      (node (ref "U5") (pin "10") (pinfunction "+IN_10") (pintype "input"))
      (node (ref "U5") (pin "12") (pinfunction "+IN_12") (pintype "input"))
      (node (ref "U5") (pin "3") (pinfunction "+IN_3") (pintype "input"))
      (node (ref "U5") (pin "5") (pinfunction "+IN_5") (pintype "input"))
    )
    (net (code "93") (name "VUSB") (class "Default")
      (node (ref "C5") (pin "1") (pinfunction "1_1") (pintype "passive"))
      (node (ref "C6") (pin "1") (pinfunction "1_1") (pintype "passive"))
      (node (ref "IC3") (pin "20") (pinfunction "VCC_20") (pintype "power_in"))
      (node (ref "IC3") (pin "4") (pinfunction "VCCIO_4") (pintype "power_in"))
      (node (ref "U$1") (pin "P6") (pinfunction "P6_P6") (pintype "bidirectional"))
    )
    (net (code "94") (name "WLS1") (class "Default")
      (node (ref "U$1") (pin "30") (pinfunction "30_30") (pintype "bidirectional"))
      (node (ref "U2") (pin "1") (pinfunction "CH0_1") (pintype "input"))
    )
    (net (code "95") (name "WLS2") (class "Default")
      (node (ref "U$1") (pin "31") (pinfunction "31_31") (pintype "bidirectional"))
      (node (ref "U2") (pin "2") (pinfunction "CH1_2") (pintype "input"))
    )
    (net (code "96") (name "WLS3") (class "Default")
      (node (ref "U$1") (pin "32") (pinfunction "32_32") (pintype "bidirectional"))
      (node (ref "U2") (pin "3") (pinfunction "CH2_3") (pintype "input"))
    )
    (net (code "97") (name "WLS4") (class "Default")
      (node (ref "U$5") (pin "35") (pinfunction "35_35") (pintype "bidirectional"))
    )
    (net (code "98") (name "WLS5") (class "Default")
      (node (ref "U$5") (pin "34") (pinfunction "34_34") (pintype "bidirectional"))
    )
    (net (code "99") (name "WLS6") (class "Default")
      (node (ref "U$5") (pin "31") (pinfunction "31_31") (pintype "bidirectional"))
    )
    (net (code "100") (name "WLS7") (class "Default")
      (node (ref "U$5") (pin "32") (pinfunction "32_32") (pintype "bidirectional"))
    )
    (net (code "101") (name "WLSD") (class "Default")
      (node (ref "RASPPI") (pin "38") (pinfunction "20_38") (pintype "bidirectional"))
      (node (ref "U$1") (pin "40") (pinfunction "40_40") (pintype "bidirectional"))
    )
    (net (code "102") (name "XADC1") (class "Default")
      (node (ref "U$5") (pin "2") (pinfunction "2_2") (pintype "bidirectional"))
      (node (ref "U3") (pin "3") (pinfunction "CH2_3") (pintype "input"))
    )
    (net (code "103") (name "XADC2") (class "Default")
      (node (ref "U$5") (pin "3") (pinfunction "3_3") (pintype "bidirectional"))
      (node (ref "U3") (pin "4") (pinfunction "CH3_4") (pintype "input"))
    )
    (net (code "104") (name "XADC3") (class "Default")
      (node (ref "U$5") (pin "4") (pinfunction "4_4") (pintype "bidirectional"))
      (node (ref "U3") (pin "5") (pinfunction "CH4_5") (pintype "input"))
    )
    (net (code "105") (name "XADC4") (class "Default")
      (node (ref "U$5") (pin "5") (pinfunction "5_5") (pintype "bidirectional"))
      (node (ref "U3") (pin "6") (pinfunction "CH5_6") (pintype "input"))
    )
    (net (code "106") (name "XADC5") (class "Default")
      (node (ref "U$5") (pin "6") (pinfunction "6_6") (pintype "bidirectional"))
      (node (ref "U3") (pin "7") (pinfunction "CH6_7") (pintype "input"))
    )
    (net (code "107") (name "XADC6") (class "Default")
      (node (ref "U$5") (pin "7") (pinfunction "7_7") (pintype "bidirectional"))
      (node (ref "U3") (pin "8") (pinfunction "CH7_8") (pintype "input"))
    )
    (net (code "108") (name "XGPIO1") (class "Default")
      (node (ref "IC5") (pin "8") (pinfunction "GPB7_8") (pintype "bidirectional"))
      (node (ref "U$5") (pin "8") (pinfunction "8_8") (pintype "bidirectional"))
    )
    (net (code "109") (name "XGPIO2") (class "Default")
      (node (ref "IC6") (pin "21") (pinfunction "GPA0_21") (pintype "bidirectional"))
      (node (ref "U$5") (pin "9") (pinfunction "9_9") (pintype "bidirectional"))
    )
    (net (code "110") (name "XGPIO3") (class "Default")
      (node (ref "IC6") (pin "22") (pinfunction "GPA1_22") (pintype "bidirectional"))
      (node (ref "U$5") (pin "10") (pinfunction "10_10") (pintype "bidirectional"))
    )
    (net (code "111") (name "XGPIO4") (class "Default")
      (node (ref "IC6") (pin "23") (pinfunction "GPA2_23") (pintype "bidirectional"))
      (node (ref "U$5") (pin "11") (pinfunction "11_11") (pintype "bidirectional"))
    )
    (net (code "112") (name "XGPIO5") (class "Default")
      (node (ref "IC6") (pin "24") (pinfunction "GPA3_24") (pintype "bidirectional"))
      (node (ref "U$5") (pin "12") (pinfunction "12_12") (pintype "bidirectional"))
    )
    (net (code "113") (name "XGPIO6") (class "Default")
      (node (ref "IC6") (pin "25") (pinfunction "GPA4_25") (pintype "bidirectional"))
      (node (ref "U$5") (pin "13") (pinfunction "13_13") (pintype "bidirectional"))
    )
    (net (code "114") (name "XGPIO7") (class "Default")
      (node (ref "IC6") (pin "26") (pinfunction "GPA5_26") (pintype "bidirectional"))
      (node (ref "U$5") (pin "14") (pinfunction "14_14") (pintype "bidirectional"))
    )
    (net (code "115") (name "XGPIO8") (class "Default")
      (node (ref "IC6") (pin "27") (pinfunction "GPA6_27") (pintype "bidirectional"))
      (node (ref "U$5") (pin "15") (pinfunction "15_15") (pintype "bidirectional"))
    )
    (net (code "116") (name "XGPIO9") (class "Default")
      (node (ref "IC6") (pin "28") (pinfunction "GPA7_28") (pintype "bidirectional"))
      (node (ref "U$5") (pin "16") (pinfunction "16_16") (pintype "bidirectional"))
    )
    (net (code "117") (name "XGPIO10") (class "Default")
      (node (ref "IC6") (pin "1") (pinfunction "GPB0_1") (pintype "bidirectional"))
      (node (ref "U$5") (pin "17") (pinfunction "17_17") (pintype "bidirectional"))
    )
    (net (code "118") (name "XGPIO11") (class "Default")
      (node (ref "IC6") (pin "2") (pinfunction "GPB1_2") (pintype "bidirectional"))
      (node (ref "U$5") (pin "18") (pinfunction "18_18") (pintype "bidirectional"))
    )
    (net (code "119") (name "XGPIO12") (class "Default")
      (node (ref "IC6") (pin "3") (pinfunction "GPB2_3") (pintype "bidirectional"))
      (node (ref "U$5") (pin "19") (pinfunction "19_19") (pintype "bidirectional"))
    )
    (net (code "120") (name "XGPIO13") (class "Default")
      (node (ref "IC6") (pin "4") (pinfunction "GPB3_4") (pintype "bidirectional"))
      (node (ref "U$5") (pin "22") (pinfunction "22_22") (pintype "bidirectional"))
    )
    (net (code "121") (name "XGPIO14") (class "Default")
      (node (ref "IC6") (pin "5") (pinfunction "GPB4_5") (pintype "bidirectional"))
      (node (ref "U$5") (pin "23") (pinfunction "23_23") (pintype "bidirectional"))
    )
    (net (code "122") (name "XGPIO15") (class "Default")
      (node (ref "IC6") (pin "6") (pinfunction "GPB5_6") (pintype "bidirectional"))
      (node (ref "U$5") (pin "24") (pinfunction "24_24") (pintype "bidirectional"))
    )
    (net (code "123") (name "XGPIO16") (class "Default")
      (node (ref "IC6") (pin "7") (pinfunction "GPB6_7") (pintype "bidirectional"))
      (node (ref "U$5") (pin "25") (pinfunction "25_25") (pintype "bidirectional"))
    )
    (net (code "124") (name "XGPIO17") (class "Default")
      (node (ref "IC6") (pin "8") (pinfunction "GPB7_8") (pintype "bidirectional"))
      (node (ref "U$5") (pin "26") (pinfunction "26_26") (pintype "bidirectional"))
    )
    (net (code "125") (name "unconnected-(IC3-3V3OUT-Pad17)") (class "Default")
      (node (ref "IC3") (pin "17") (pinfunction "3V3OUT_17") (pintype "output"))
    )
    (net (code "126") (name "unconnected-(IC3-CBUS2-Pad13)") (class "Default")
      (node (ref "IC3") (pin "13") (pinfunction "CBUS2_13") (pintype "bidirectional"))
    )
    (net (code "127") (name "unconnected-(IC3-CBUS3-Pad14)") (class "Default")
      (node (ref "IC3") (pin "14") (pinfunction "CBUS3_14") (pintype "bidirectional"))
    )
    (net (code "128") (name "unconnected-(IC3-CBUS4-Pad12)") (class "Default")
      (node (ref "IC3") (pin "12") (pinfunction "CBUS4_12") (pintype "bidirectional"))
    )
    (net (code "129") (name "unconnected-(IC3-OSCI-Pad27)") (class "Default")
      (node (ref "IC3") (pin "27") (pinfunction "OSCI_27") (pintype "input"))
    )
    (net (code "130") (name "unconnected-(IC3-OSCO-Pad28)") (class "Default")
      (node (ref "IC3") (pin "28") (pinfunction "OSCO_28") (pintype "output"))
    )
    (net (code "131") (name "unconnected-(IC3-~{CTS}-Pad11)") (class "Default")
      (node (ref "IC3") (pin "11") (pinfunction "~{CTS}_11") (pintype "input"))
    )
    (net (code "132") (name "unconnected-(IC3-~{DCD}-Pad10)") (class "Default")
      (node (ref "IC3") (pin "10") (pinfunction "~{DCD}_10") (pintype "input"))
    )
    (net (code "133") (name "unconnected-(IC3-~{DSR}-Pad9)") (class "Default")
      (node (ref "IC3") (pin "9") (pinfunction "~{DSR}_9") (pintype "input"))
    )
    (net (code "134") (name "unconnected-(IC3-~{DTR}-Pad2)") (class "Default")
      (node (ref "IC3") (pin "2") (pinfunction "~{DTR}_2") (pintype "output"))
    )
    (net (code "135") (name "unconnected-(IC3-~{RESET}-Pad19)") (class "Default")
      (node (ref "IC3") (pin "19") (pinfunction "~{RESET}_19") (pintype "input"))
    )
    (net (code "136") (name "unconnected-(IC3-~{RI}-Pad6)") (class "Default")
      (node (ref "IC3") (pin "6") (pinfunction "~{RI}_6") (pintype "input"))
    )
    (net (code "137") (name "unconnected-(IC3-~{RTS}-Pad3)") (class "Default")
      (node (ref "IC3") (pin "3") (pinfunction "~{RTS}_3") (pintype "output"))
    )
    (net (code "138") (name "unconnected-(IC4-R2IN-Pad8)") (class "Default")
      (node (ref "IC4") (pin "8") (pinfunction "R2IN_8") (pintype "input"))
    )
    (net (code "139") (name "unconnected-(IC4-R2OUT-Pad9)") (class "Default")
      (node (ref "IC4") (pin "9") (pinfunction "R2OUT_9") (pintype "output"))
    )
    (net (code "140") (name "unconnected-(IC4-T2IN-Pad10)") (class "Default")
      (node (ref "IC4") (pin "10") (pinfunction "T2IN_10") (pintype "input"))
    )
    (net (code "141") (name "unconnected-(IC4-T2OUT-Pad7)") (class "Default")
      (node (ref "IC4") (pin "7") (pinfunction "T2OUT_7") (pintype "output"))
    )
    (net (code "142") (name "unconnected-(IC5-INTA-Pad20)") (class "Default")
      (node (ref "IC5") (pin "20") (pinfunction "INTA_20") (pintype "output"))
    )
    (net (code "143") (name "unconnected-(IC5-INTB-Pad19)") (class "Default")
      (node (ref "IC5") (pin "19") (pinfunction "INTB_19") (pintype "output"))
    )
    (net (code "144") (name "unconnected-(IC6-INTA-Pad20)") (class "Default")
      (node (ref "IC6") (pin "20") (pinfunction "INTA_20") (pintype "output"))
    )
    (net (code "145") (name "unconnected-(IC6-INTB-Pad19)") (class "Default")
      (node (ref "IC6") (pin "19") (pinfunction "INTB_19") (pintype "output"))
    )
    (net (code "146") (name "unconnected-(RASPPI-5-2-Pad4)") (class "Default")
      (node (ref "RASPPI") (pin "4") (pinfunction "5-2_4") (pintype "bidirectional"))
    )
    (net (code "147") (name "unconnected-(RASPPI-GND2-Pad9)") (class "Default")
      (node (ref "RASPPI") (pin "9") (pinfunction "GND2_9") (pintype "bidirectional"))
    )
    (net (code "148") (name "unconnected-(RASPPI-GND4-Pad20)") (class "Default")
      (node (ref "RASPPI") (pin "20") (pinfunction "GND4_20") (pintype "bidirectional"))
    )
    (net (code "149") (name "unconnected-(RASPPI-GND5-Pad25)") (class "Default")
      (node (ref "RASPPI") (pin "25") (pinfunction "GND5_25") (pintype "bidirectional"))
    )
    (net (code "150") (name "unconnected-(RASPPI-PCM-Pad12)") (class "Default")
      (node (ref "RASPPI") (pin "12") (pinfunction "PCM_12") (pintype "bidirectional"))
    )
    (net (code "151") (name "unconnected-(RASPPI-SC-Pad28)") (class "Default")
      (node (ref "RASPPI") (pin "28") (pinfunction "SC_28") (pintype "bidirectional"))
    )
    (net (code "152") (name "unconnected-(RASPPI-SD-Pad27)") (class "Default")
      (node (ref "RASPPI") (pin "27") (pinfunction "SD_27") (pintype "bidirectional"))
    )
    (net (code "153") (name "unconnected-(U$1-Pad1)") (class "Default")
      (node (ref "U$1") (pin "1") (pinfunction "1_1") (pintype "bidirectional"))
    )
    (net (code "154") (name "unconnected-(U$1-Pad2)") (class "Default")
      (node (ref "U$1") (pin "2") (pinfunction "2_2") (pintype "bidirectional"))
    )
    (net (code "155") (name "unconnected-(U$1-Pad3)") (class "Default")
      (node (ref "U$1") (pin "3") (pinfunction "3_3") (pintype "bidirectional"))
    )
    (net (code "156") (name "unconnected-(U$1-Pad4)") (class "Default")
      (node (ref "U$1") (pin "4") (pinfunction "4_4") (pintype "bidirectional"))
    )
    (net (code "157") (name "unconnected-(U$1-Pad5)") (class "Default")
      (node (ref "U$1") (pin "5") (pinfunction "5_5") (pintype "bidirectional"))
    )
    (net (code "158") (name "unconnected-(U$1-Pad6)") (class "Default")
      (node (ref "U$1") (pin "6") (pinfunction "6_6") (pintype "bidirectional"))
    )
    (net (code "159") (name "unconnected-(U$1-Pad7)") (class "Default")
      (node (ref "U$1") (pin "7") (pinfunction "7_7") (pintype "bidirectional"))
    )
    (net (code "160") (name "unconnected-(U$1-Pad8)") (class "Default")
      (node (ref "U$1") (pin "8") (pinfunction "8_8") (pintype "bidirectional"))
    )
    (net (code "161") (name "unconnected-(U$1-Pad9)") (class "Default")
      (node (ref "U$1") (pin "9") (pinfunction "9_9") (pintype "bidirectional"))
    )
    (net (code "162") (name "unconnected-(U$1-Pad10)") (class "Default")
      (node (ref "U$1") (pin "10") (pinfunction "10_10") (pintype "bidirectional"))
    )
    (net (code "163") (name "unconnected-(U$1-Pad11)") (class "Default")
      (node (ref "U$1") (pin "11") (pinfunction "11_11") (pintype "bidirectional"))
    )
    (net (code "164") (name "unconnected-(U$1-Pad12)") (class "Default")
      (node (ref "U$1") (pin "12") (pinfunction "12_12") (pintype "bidirectional"))
    )
    (net (code "165") (name "unconnected-(U$1-Pad13)") (class "Default")
      (node (ref "U$1") (pin "13") (pinfunction "13_13") (pintype "bidirectional"))
    )
    (net (code "166") (name "unconnected-(U$1-Pad14)") (class "Default")
      (node (ref "U$1") (pin "14") (pinfunction "14_14") (pintype "bidirectional"))
    )
    (net (code "167") (name "unconnected-(U$1-Pad15)") (class "Default")
      (node (ref "U$1") (pin "15") (pinfunction "15_15") (pintype "bidirectional"))
    )
    (net (code "168") (name "unconnected-(U$1-Pad16)") (class "Default")
      (node (ref "U$1") (pin "16") (pinfunction "16_16") (pintype "bidirectional"))
    )
    (net (code "169") (name "unconnected-(U$1-Pad17)") (class "Default")
      (node (ref "U$1") (pin "17") (pinfunction "17_17") (pintype "bidirectional"))
    )
    (net (code "170") (name "unconnected-(U$1-Pad18)") (class "Default")
      (node (ref "U$1") (pin "18") (pinfunction "18_18") (pintype "bidirectional"))
    )
    (net (code "171") (name "unconnected-(U$1-Pad19)") (class "Default")
      (node (ref "U$1") (pin "19") (pinfunction "19_19") (pintype "bidirectional"))
    )
    (net (code "172") (name "unconnected-(U$1-Pad20)") (class "Default")
      (node (ref "U$1") (pin "20") (pinfunction "20_20") (pintype "bidirectional"))
    )
    (net (code "173") (name "unconnected-(U$1-Pad21)") (class "Default")
      (node (ref "U$1") (pin "21") (pinfunction "21_21") (pintype "bidirectional"))
    )
    (net (code "174") (name "unconnected-(U$1-Pad35)") (class "Default")
      (node (ref "U$1") (pin "35") (pinfunction "35_35") (pintype "bidirectional"))
    )
    (net (code "175") (name "unconnected-(U$1-Pad36)") (class "Default")
      (node (ref "U$1") (pin "36") (pinfunction "36_36") (pintype "bidirectional"))
    )
    (net (code "176") (name "unconnected-(U$1-Pad37)") (class "Default")
      (node (ref "U$1") (pin "37") (pinfunction "37_37") (pintype "bidirectional"))
    )
    (net (code "177") (name "unconnected-(U$1-Pad38)") (class "Default")
      (node (ref "U$1") (pin "38") (pinfunction "38_38") (pintype "bidirectional"))
    )
    (net (code "178") (name "unconnected-(U$1-Pad39)") (class "Default")
      (node (ref "U$1") (pin "39") (pinfunction "39_39") (pintype "bidirectional"))
    )
    (net (code "179") (name "unconnected-(U$1-Pad47)") (class "Default")
      (node (ref "U$1") (pin "47") (pinfunction "47_47") (pintype "bidirectional"))
    )
    (net (code "180") (name "unconnected-(U$1-Pad48)") (class "Default")
      (node (ref "U$1") (pin "48") (pinfunction "48_48") (pintype "bidirectional"))
    )
    (net (code "181") (name "unconnected-(U$1-Pad49)") (class "Default")
      (node (ref "U$1") (pin "49") (pinfunction "49_49") (pintype "bidirectional"))
    )
    (net (code "182") (name "unconnected-(U$1-Pad57)") (class "Default")
      (node (ref "U$1") (pin "57") (pinfunction "57_57") (pintype "bidirectional"))
    )
    (net (code "183") (name "unconnected-(U$1-Pad58)") (class "Default")
      (node (ref "U$1") (pin "58") (pinfunction "58_58") (pintype "bidirectional"))
    )
    (net (code "184") (name "unconnected-(U$1-Pad59)") (class "Default")
      (node (ref "U$1") (pin "59") (pinfunction "59_59") (pintype "bidirectional"))
    )
    (net (code "185") (name "unconnected-(U$1-Pad60)") (class "Default")
      (node (ref "U$1") (pin "60") (pinfunction "60_60") (pintype "bidirectional"))
    )
    (net (code "186") (name "unconnected-(U$1-Pad61)") (class "Default")
      (node (ref "U$1") (pin "61") (pinfunction "61_61") (pintype "bidirectional"))
    )
    (net (code "187") (name "unconnected-(U$1-Pad64)") (class "Default")
      (node (ref "U$1") (pin "64") (pinfunction "64_64") (pintype "bidirectional"))
    )
    (net (code "188") (name "unconnected-(U$1-Pad65)") (class "Default")
      (node (ref "U$1") (pin "65") (pinfunction "65_65") (pintype "bidirectional"))
    )
    (net (code "189") (name "unconnected-(U$1-Pad66)") (class "Default")
      (node (ref "U$1") (pin "66") (pinfunction "66_66") (pintype "bidirectional"))
    )
    (net (code "190") (name "unconnected-(U$1-Pad67)") (class "Default")
      (node (ref "U$1") (pin "67") (pinfunction "67_67") (pintype "bidirectional"))
    )
    (net (code "191") (name "unconnected-(U$1-Pad68)") (class "Default")
      (node (ref "U$1") (pin "68") (pinfunction "68_68") (pintype "bidirectional"))
    )
    (net (code "192") (name "unconnected-(U$1-Pad72)") (class "Default")
      (node (ref "U$1") (pin "72") (pinfunction "72_72") (pintype "bidirectional"))
    )
    (net (code "193") (name "unconnected-(U$1-PadP1)") (class "Default")
      (node (ref "U$1") (pin "P1") (pinfunction "P1_P1") (pintype "bidirectional"))
    )
    (net (code "194") (name "unconnected-(U$1-PadP8)") (class "Default")
      (node (ref "U$1") (pin "P8") (pinfunction "P8_P8") (pintype "bidirectional"))
    )
    (net (code "195") (name "unconnected-(U$1-PadP9)") (class "Default")
      (node (ref "U$1") (pin "P9") (pinfunction "P9_P9") (pintype "bidirectional"))
    )
    (net (code "196") (name "unconnected-(U$1-PadP10)") (class "Default")
      (node (ref "U$1") (pin "P10") (pinfunction "P10_P10") (pintype "bidirectional"))
    )
    (net (code "197") (name "unconnected-(U$1-PadP17)") (class "Default")
      (node (ref "U$1") (pin "P17") (pinfunction "P17_P17") (pintype "bidirectional"))
    )
    (net (code "198") (name "unconnected-(U$1-PadP18)") (class "Default")
      (node (ref "U$1") (pin "P18") (pinfunction "P18_P18") (pintype "bidirectional"))
    )
    (net (code "199") (name "unconnected-(U$1-PadP19)") (class "Default")
      (node (ref "U$1") (pin "P19") (pinfunction "P19_P19") (pintype "bidirectional"))
    )
    (net (code "200") (name "unconnected-(U$1-PadP20)") (class "Default")
      (node (ref "U$1") (pin "P20") (pinfunction "P20_P20") (pintype "bidirectional"))
    )
    (net (code "201") (name "unconnected-(U$1-PadP21)") (class "Default")
      (node (ref "U$1") (pin "P21") (pinfunction "P21_P21") (pintype "bidirectional"))
    )
    (net (code "202") (name "unconnected-(U$1-PadP22)") (class "Default")
      (node (ref "U$1") (pin "P22") (pinfunction "P22_P22") (pintype "bidirectional"))
    )
    (net (code "203") (name "unconnected-(U$1-PadP23)") (class "Default")
      (node (ref "U$1") (pin "P23") (pinfunction "P23_P23") (pintype "bidirectional"))
    )
    (net (code "204") (name "unconnected-(U$1-PadP24)") (class "Default")
      (node (ref "U$1") (pin "P24") (pinfunction "P24_P24") (pintype "bidirectional"))
    )
    (net (code "205") (name "unconnected-(U$1-PadP25)") (class "Default")
      (node (ref "U$1") (pin "P25") (pinfunction "P25_P25") (pintype "bidirectional"))
    )
    (net (code "206") (name "unconnected-(U$1-PadP26)") (class "Default")
      (node (ref "U$1") (pin "P26") (pinfunction "P26_P26") (pintype "bidirectional"))
    )
    (net (code "207") (name "unconnected-(U$1-PadP27)") (class "Default")
      (node (ref "U$1") (pin "P27") (pinfunction "P27_P27") (pintype "bidirectional"))
    )
    (net (code "208") (name "unconnected-(U$1-PadP28)") (class "Default")
      (node (ref "U$1") (pin "P28") (pinfunction "P28_P28") (pintype "bidirectional"))
    )
    (net (code "209") (name "unconnected-(U$1-PadP29)") (class "Default")
      (node (ref "U$1") (pin "P29") (pinfunction "P29_P29") (pintype "bidirectional"))
    )
    (net (code "210") (name "unconnected-(U$1-PadP30)") (class "Default")
      (node (ref "U$1") (pin "P30") (pinfunction "P30_P30") (pintype "bidirectional"))
    )
    (net (code "211") (name "unconnected-(U$1-PadP31)") (class "Default")
      (node (ref "U$1") (pin "P31") (pinfunction "P31_P31") (pintype "bidirectional"))
    )
    (net (code "212") (name "unconnected-(U$1-PadP32)") (class "Default")
      (node (ref "U$1") (pin "P32") (pinfunction "P32_P32") (pintype "bidirectional"))
    )
    (net (code "213") (name "unconnected-(U$1-PadP33)") (class "Default")
      (node (ref "U$1") (pin "P33") (pinfunction "P33_P33") (pintype "bidirectional"))
    )
    (net (code "214") (name "unconnected-(U$1-PadP34)") (class "Default")
      (node (ref "U$1") (pin "P34") (pinfunction "P34_P34") (pintype "bidirectional"))
    )
    (net (code "215") (name "unconnected-(U$1-PadP35)") (class "Default")
      (node (ref "U$1") (pin "P35") (pinfunction "P35_P35") (pintype "bidirectional"))
    )
    (net (code "216") (name "unconnected-(U$1-PadP36)") (class "Default")
      (node (ref "U$1") (pin "P36") (pinfunction "P36_P36") (pintype "bidirectional"))
    )
    (net (code "217") (name "unconnected-(U$1-PadP37)") (class "Default")
      (node (ref "U$1") (pin "P37") (pinfunction "P37_P37") (pintype "bidirectional"))
    )
    (net (code "218") (name "unconnected-(U$1-PadP38)") (class "Default")
      (node (ref "U$1") (pin "P38") (pinfunction "P38_P38") (pintype "bidirectional"))
    )
    (net (code "219") (name "unconnected-(U$1-PadP39)") (class "Default")
      (node (ref "U$1") (pin "P39") (pinfunction "P39_P39") (pintype "bidirectional"))
    )
    (net (code "220") (name "unconnected-(U$1-PadP40)") (class "Default")
      (node (ref "U$1") (pin "P40") (pinfunction "P40_P40") (pintype "bidirectional"))
    )
    (net (code "221") (name "unconnected-(U$1-PadP41)") (class "Default")
      (node (ref "U$1") (pin "P41") (pinfunction "P41_P41") (pintype "bidirectional"))
    )
    (net (code "222") (name "unconnected-(U$1-PadP42)") (class "Default")
      (node (ref "U$1") (pin "P42") (pinfunction "P42_P42") (pintype "bidirectional"))
    )
    (net (code "223") (name "unconnected-(U$1-PadP43)") (class "Default")
      (node (ref "U$1") (pin "P43") (pinfunction "P43_P43") (pintype "bidirectional"))
    )
    (net (code "224") (name "unconnected-(U$1-PadP44)") (class "Default")
      (node (ref "U$1") (pin "P44") (pinfunction "P44_P44") (pintype "bidirectional"))
    )
    (net (code "225") (name "unconnected-(U$1-PadP45)") (class "Default")
      (node (ref "U$1") (pin "P45") (pinfunction "P45_P45") (pintype "bidirectional"))
    )
    (net (code "226") (name "unconnected-(U$1-PadP46)") (class "Default")
      (node (ref "U$1") (pin "P46") (pinfunction "P46_P46") (pintype "bidirectional"))
    )
    (net (code "227") (name "unconnected-(U$1-PadP47)") (class "Default")
      (node (ref "U$1") (pin "P47") (pinfunction "P47_P47") (pintype "bidirectional"))
    )
    (net (code "228") (name "unconnected-(U$1-PadP48)") (class "Default")
      (node (ref "U$1") (pin "P48") (pinfunction "P48_P48") (pintype "bidirectional"))
    )
    (net (code "229") (name "unconnected-(U$1-PadP49)") (class "Default")
      (node (ref "U$1") (pin "P49") (pinfunction "P49_P49") (pintype "bidirectional"))
    )
    (net (code "230") (name "unconnected-(U$1-PadP50)") (class "Default")
      (node (ref "U$1") (pin "P50") (pinfunction "P50_P50") (pintype "bidirectional"))
    )
    (net (code "231") (name "unconnected-(U$1-PadP51)") (class "Default")
      (node (ref "U$1") (pin "P51") (pinfunction "P51_P51") (pintype "bidirectional"))
    )
    (net (code "232") (name "unconnected-(U$1-PadP52)") (class "Default")
      (node (ref "U$1") (pin "P52") (pinfunction "P52_P52") (pintype "bidirectional"))
    )
    (net (code "233") (name "unconnected-(U$1-PadP53)") (class "Default")
      (node (ref "U$1") (pin "P53") (pinfunction "P53_P53") (pintype "bidirectional"))
    )
    (net (code "234") (name "unconnected-(U$1-PadP54)") (class "Default")
      (node (ref "U$1") (pin "P54") (pinfunction "P54_P54") (pintype "bidirectional"))
    )
    (net (code "235") (name "unconnected-(U$1-PadP55)") (class "Default")
      (node (ref "U$1") (pin "P55") (pinfunction "P55_P55") (pintype "bidirectional"))
    )
    (net (code "236") (name "unconnected-(U$1-PadP57)") (class "Default")
      (node (ref "U$1") (pin "P57") (pinfunction "P57_P57") (pintype "bidirectional"))
    )
    (net (code "237") (name "unconnected-(U$1-PadP58)") (class "Default")
      (node (ref "U$1") (pin "P58") (pinfunction "P58_P58") (pintype "bidirectional"))
    )
    (net (code "238") (name "unconnected-(U$1-PadP59)") (class "Default")
      (node (ref "U$1") (pin "P59") (pinfunction "P59_P59") (pintype "bidirectional"))
    )
    (net (code "239") (name "unconnected-(U$1-PadP60)") (class "Default")
      (node (ref "U$1") (pin "P60") (pinfunction "P60_P60") (pintype "bidirectional"))
    )
    (net (code "240") (name "unconnected-(U$1-PadP61)") (class "Default")
      (node (ref "U$1") (pin "P61") (pinfunction "P61_P61") (pintype "bidirectional"))
    )
    (net (code "241") (name "unconnected-(U$1-PadP62)") (class "Default")
      (node (ref "U$1") (pin "P62") (pinfunction "P62_P62") (pintype "bidirectional"))
    )
    (net (code "242") (name "unconnected-(U$1-PadP63)") (class "Default")
      (node (ref "U$1") (pin "P63") (pinfunction "P63_P63") (pintype "bidirectional"))
    )
    (net (code "243") (name "unconnected-(U$1-PadP64)") (class "Default")
      (node (ref "U$1") (pin "P64") (pinfunction "P64_P64") (pintype "bidirectional"))
    )
    (net (code "244") (name "unconnected-(U$1-PadP65)") (class "Default")
      (node (ref "U$1") (pin "P65") (pinfunction "P65_P65") (pintype "bidirectional"))
    )
    (net (code "245") (name "unconnected-(U$1-PadP66)") (class "Default")
      (node (ref "U$1") (pin "P66") (pinfunction "P66_P66") (pintype "bidirectional"))
    )
    (net (code "246") (name "unconnected-(U$1-PadP67)") (class "Default")
      (node (ref "U$1") (pin "P67") (pinfunction "P67_P67") (pintype "bidirectional"))
    )
    (net (code "247") (name "unconnected-(U$1-PadP68)") (class "Default")
      (node (ref "U$1") (pin "P68") (pinfunction "P68_P68") (pintype "bidirectional"))
    )
    (net (code "248") (name "unconnected-(U$1-PadP69)") (class "Default")
      (node (ref "U$1") (pin "P69") (pinfunction "P69_P69") (pintype "bidirectional"))
    )
    (net (code "249") (name "unconnected-(U$1-PadP70)") (class "Default")
      (node (ref "U$1") (pin "P70") (pinfunction "P70_P70") (pintype "bidirectional"))
    )
    (net (code "250") (name "unconnected-(U$1-PadP71)") (class "Default")
      (node (ref "U$1") (pin "P71") (pinfunction "P71_P71") (pintype "bidirectional"))
    )
    (net (code "251") (name "unconnected-(U$1-PadP72)") (class "Default")
      (node (ref "U$1") (pin "P72") (pinfunction "P72_P72") (pintype "bidirectional"))
    )
    (net (code "252") (name "unconnected-(U$1-PadP73)") (class "Default")
      (node (ref "U$1") (pin "P73") (pinfunction "P73_P73") (pintype "bidirectional"))
    )
    (net (code "253") (name "unconnected-(U$1-PadP74)") (class "Default")
      (node (ref "U$1") (pin "P74") (pinfunction "P74_P74") (pintype "bidirectional"))
    )
    (net (code "254") (name "unconnected-(U4-OUT-Pad4)") (class "Default")
      (node (ref "U4") (pin "4") (pinfunction "OUT_4") (pintype "output"))
    )
  )
)
